# RS422_Breakout.net
KiCad netlist of a schematic drawn in Altium Designer
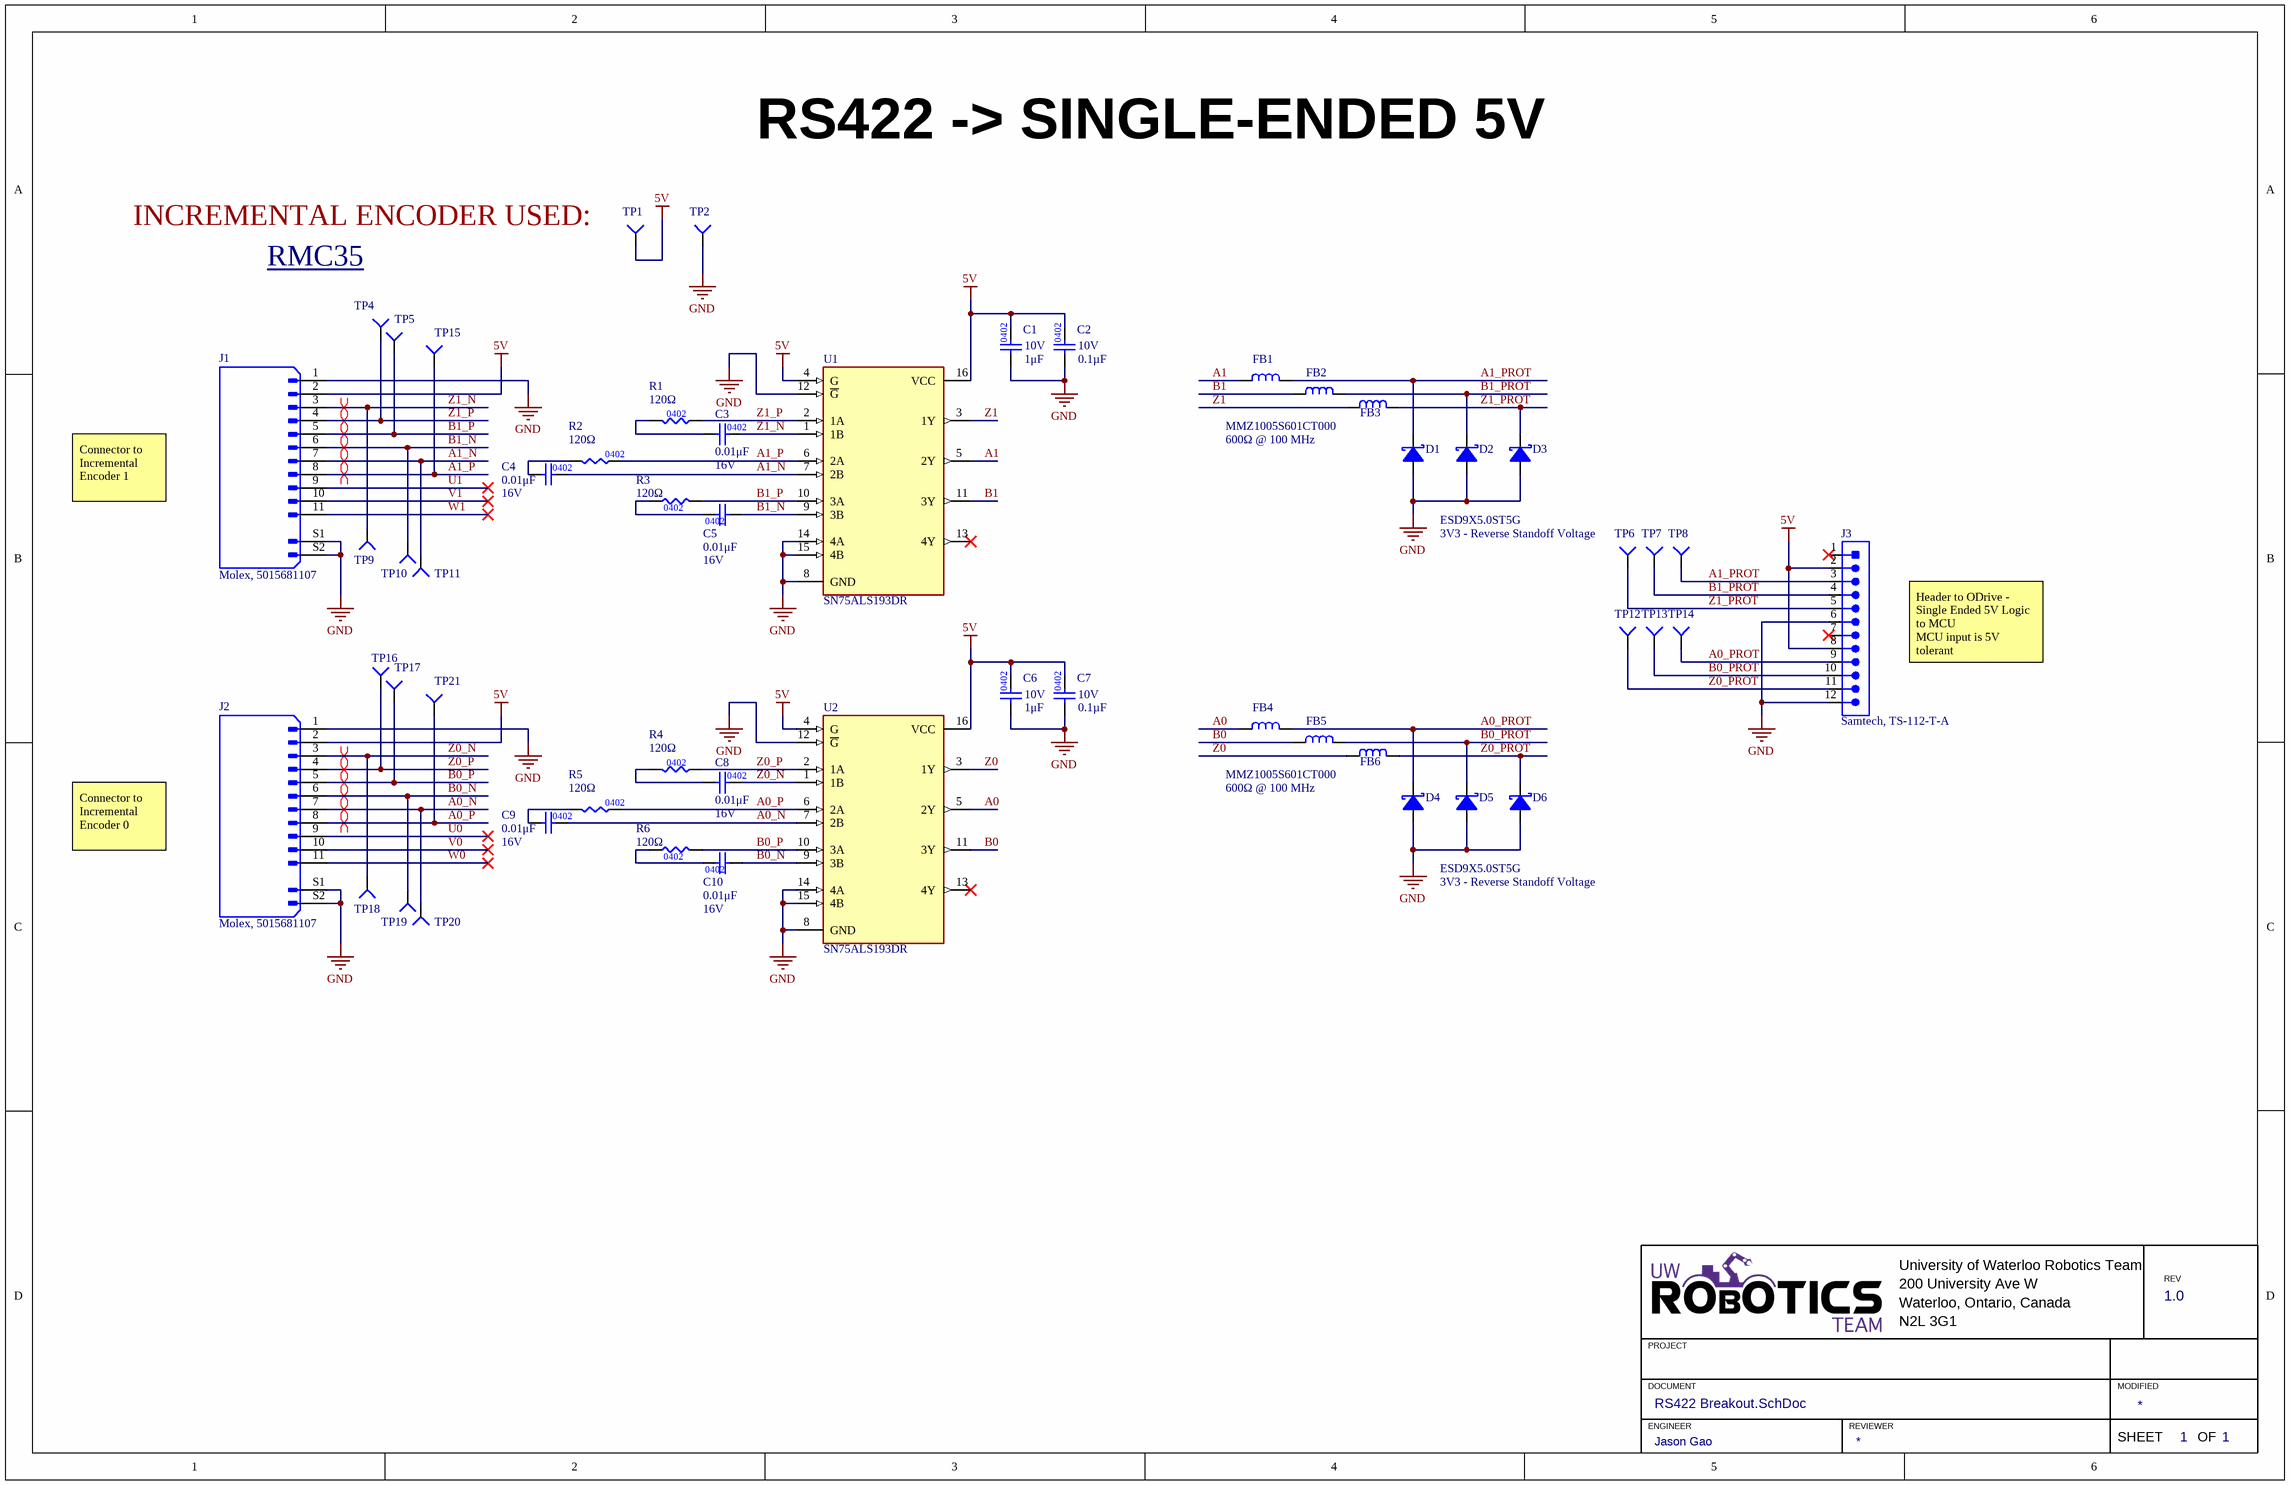
[diagram p0: RS422 Breakout.SchDoc]

(export (version "E")
  (design (tool "Eeschema 10.0.6"))
  (components
    (comp (ref "C1")
      (value "CAP_1UF_10V_0402_X5R")
      (footprint "CAP0402")
      (description "CAP CER 1UF 10V X5R 0402")
      (fields
        (field (name "MANUFACTURER") "Kyocera AVX")
        (field (name "MANUFACTURER PART NUMBER") "0402ZD105MAT2A")
        (field (name "CAPACITANCE") "1μF")
        (field (name "RATED DC VOLTAGE (URDC)") "10V")
      )
      (libsource (lib "UWRT_Schematic_Library_2020") (part "CAP_1UF_10V_0402_X5R"))
    )
    (comp (ref "C2")
      (value "0.1µF")
      (footprint "CAP0402")
      (description "CAP CER 0.1UF 10V X7R 0402")
      (fields (field (name "VOLTAGE RATING") "10V") (field (name "Comment") "CAP_0.1uF_10V_0402"))
      (libsource (lib "UWRT_Schematic_Library_2020") (part "CAP_0.1uF_10V_0402"))
    )
    (comp (ref "C3")
      (value "CAP_0.01uF_16V_X7R_0402")
      (footprint "CAP0402")
      (description "CAP CER 0.01uF 16V X7R 0402")
      (fields
        (field (name "MANUFACTURER") "KEMET")
        (field (name "MANUFACTURER PART NUMBER") "C0402C103J4RACTU")
        (field (name "CAPACITANCE") "0.01μF")
        (field (name "VOLTAGE RATING") "16V")
      )
      (libsource (lib "UWRT_Schematic_Library_2020") (part "CAP_0.01uF_16V_X7R_0402"))
    )
    (comp (ref "C4")
      (value "CAP_0.01uF_16V_X7R_0402")
      (footprint "CAP0402")
      (description "CAP CER 0.01uF 16V X7R 0402")
      (fields
        (field (name "MANUFACTURER") "KEMET")
        (field (name "MANUFACTURER PART NUMBER") "C0402C103J4RACTU")
        (field (name "CAPACITANCE") "0.01μF")
        (field (name "VOLTAGE RATING") "16V")
      )
      (libsource (lib "UWRT_Schematic_Library_2020") (part "CAP_0.01uF_16V_X7R_0402"))
    )
    (comp (ref "C5")
      (value "CAP_0.01uF_16V_X7R_0402")
      (footprint "CAP0402")
      (description "CAP CER 0.01uF 16V X7R 0402")
      (fields
        (field (name "MANUFACTURER") "KEMET")
        (field (name "MANUFACTURER PART NUMBER") "C0402C103J4RACTU")
        (field (name "CAPACITANCE") "0.01μF")
        (field (name "VOLTAGE RATING") "16V")
      )
      (libsource (lib "UWRT_Schematic_Library_2020") (part "CAP_0.01uF_16V_X7R_0402"))
    )
    (comp (ref "C6")
      (value "CAP_1UF_10V_0402_X5R")
      (footprint "CAP0402")
      (description "CAP CER 1UF 10V X5R 0402")
      (fields
        (field (name "MANUFACTURER") "Kyocera AVX")
        (field (name "MANUFACTURER PART NUMBER") "0402ZD105MAT2A")
        (field (name "CAPACITANCE") "1μF")
        (field (name "RATED DC VOLTAGE (URDC)") "10V")
      )
      (libsource (lib "UWRT_Schematic_Library_2020") (part "CAP_1UF_10V_0402_X5R"))
    )
    (comp (ref "C7")
      (value "0.1µF")
      (footprint "CAP0402")
      (description "CAP CER 0.1UF 10V X7R 0402")
      (fields (field (name "VOLTAGE RATING") "10V") (field (name "Comment") "CAP_0.1uF_10V_0402"))
      (libsource (lib "UWRT_Schematic_Library_2020") (part "CAP_0.1uF_10V_0402"))
    )
    (comp (ref "C8")
      (value "CAP_0.01uF_16V_X7R_0402")
      (footprint "CAP0402")
      (description "CAP CER 0.01uF 16V X7R 0402")
      (fields
        (field (name "MANUFACTURER") "KEMET")
        (field (name "MANUFACTURER PART NUMBER") "C0402C103J4RACTU")
        (field (name "CAPACITANCE") "0.01μF")
        (field (name "VOLTAGE RATING") "16V")
      )
      (libsource (lib "UWRT_Schematic_Library_2020") (part "CAP_0.01uF_16V_X7R_0402"))
    )
    (comp (ref "C9")
      (value "CAP_0.01uF_16V_X7R_0402")
      (footprint "CAP0402")
      (description "CAP CER 0.01uF 16V X7R 0402")
      (fields
        (field (name "MANUFACTURER") "KEMET")
        (field (name "MANUFACTURER PART NUMBER") "C0402C103J4RACTU")
        (field (name "CAPACITANCE") "0.01μF")
        (field (name "VOLTAGE RATING") "16V")
      )
      (libsource (lib "UWRT_Schematic_Library_2020") (part "CAP_0.01uF_16V_X7R_0402"))
    )
    (comp (ref "C10")
      (value "CAP_0.01uF_16V_X7R_0402")
      (footprint "CAP0402")
      (description "CAP CER 0.01uF 16V X7R 0402")
      (fields
        (field (name "MANUFACTURER") "KEMET")
        (field (name "MANUFACTURER PART NUMBER") "C0402C103J4RACTU")
        (field (name "CAPACITANCE") "0.01μF")
        (field (name "VOLTAGE RATING") "16V")
      )
      (libsource (lib "UWRT_Schematic_Library_2020") (part "CAP_0.01uF_16V_X7R_0402"))
    )
    (comp (ref "D1")
      (value "TVS_DIODE_UNIDIR_5V")
      (footprint "sod-923")
      (description "TVS DIODE 5VWM 12.3VC SOD923")
      (fields (field (name "MANUFACTURER PART NUMBER 1") "ESD9X5.0ST5G"))
      (libsource (lib "UWRT_Schematic_Library_2020") (part "TVS_DIODE_UNIDIR_5V"))
    )
    (comp (ref "D2")
      (value "TVS_DIODE_UNIDIR_5V")
      (footprint "sod-923")
      (description "TVS DIODE 5VWM 12.3VC SOD923")
      (libsource (lib "UWRT_Schematic_Library_2020") (part "TVS_DIODE_UNIDIR_5V"))
    )
    (comp (ref "D3")
      (value "TVS_DIODE_UNIDIR_5V")
      (footprint "sod-923")
      (description "TVS DIODE 5VWM 12.3VC SOD923")
      (libsource (lib "UWRT_Schematic_Library_2020") (part "TVS_DIODE_UNIDIR_5V"))
    )
    (comp (ref "D4")
      (value "TVS_DIODE_UNIDIR_5V")
      (footprint "sod-923")
      (description "TVS DIODE 5VWM 12.3VC SOD923")
      (fields (field (name "MANUFACTURER PART NUMBER 1") "ESD9X5.0ST5G"))
      (libsource (lib "UWRT_Schematic_Library_2020") (part "TVS_DIODE_UNIDIR_5V"))
    )
    (comp (ref "D5")
      (value "TVS_DIODE_UNIDIR_5V")
      (footprint "sod-923")
      (description "TVS DIODE 5VWM 12.3VC SOD923")
      (libsource (lib "UWRT_Schematic_Library_2020") (part "TVS_DIODE_UNIDIR_5V"))
    )
    (comp (ref "D6")
      (value "TVS_DIODE_UNIDIR_5V")
      (footprint "sod-923")
      (description "TVS DIODE 5VWM 12.3VC SOD923")
      (libsource (lib "UWRT_Schematic_Library_2020") (part "TVS_DIODE_UNIDIR_5V"))
    )
    (comp (ref "FB1")
      (value "FERRITE_BEAD_600OHM_0402")
      (footprint "RES0402")
      (description "FIXED IND 1UH 3.8A 33 MOHM SMD")
      (libsource (lib "UWRT_Schematic_Library_2020") (part "FERRITE_BEAD_600OHM_0402"))
    )
    (comp (ref "FB2")
      (value "FERRITE_BEAD_600OHM_0402")
      (footprint "RES0402")
      (description "FIXED IND 1UH 3.8A 33 MOHM SMD")
      (fields
        (field (name "MANUFACTURER PART NUMBER 1") "MMZ1005S601CT000")
        (field (name "IMPEDANCE @ FREQUENCY") "600Ω @ 100 MHz")
      )
      (libsource (lib "UWRT_Schematic_Library_2020") (part "FERRITE_BEAD_600OHM_0402"))
    )
    (comp (ref "FB3")
      (value "FERRITE_BEAD_600OHM_0402")
      (footprint "RES0402")
      (description "FIXED IND 1UH 3.8A 33 MOHM SMD")
      (libsource (lib "UWRT_Schematic_Library_2020") (part "FERRITE_BEAD_600OHM_0402"))
    )
    (comp (ref "FB4")
      (value "FERRITE_BEAD_600OHM_0402")
      (footprint "RES0402")
      (description "FIXED IND 1UH 3.8A 33 MOHM SMD")
      (libsource (lib "UWRT_Schematic_Library_2020") (part "FERRITE_BEAD_600OHM_0402"))
    )
    (comp (ref "FB5")
      (value "FERRITE_BEAD_600OHM_0402")
      (footprint "RES0402")
      (description "FIXED IND 1UH 3.8A 33 MOHM SMD")
      (fields
        (field (name "MANUFACTURER PART NUMBER 1") "MMZ1005S601CT000")
        (field (name "IMPEDANCE @ FREQUENCY") "600Ω @ 100 MHz")
      )
      (libsource (lib "UWRT_Schematic_Library_2020") (part "FERRITE_BEAD_600OHM_0402"))
    )
    (comp (ref "FB6")
      (value "FERRITE_BEAD_600OHM_0402")
      (footprint "RES0402")
      (description "FIXED IND 1UH 3.8A 33 MOHM SMD")
      (libsource (lib "UWRT_Schematic_Library_2020") (part "FERRITE_BEAD_600OHM_0402"))
    )
    (comp (ref "J1")
      (value "CON_12M_SM_RA")
      (footprint "MOLEX-5015681107")
      (description "CONN HEADER SMD RIGHT ANGLE 1MM PITCH")
      (fields (field (name "MP") "Molex, 5015681107"))
      (libsource (lib "templocal") (part "CON_11M_SM_RA"))
    )
    (comp (ref "J2")
      (value "CON_12M_SM_RA")
      (footprint "MOLEX-5015681107")
      (description "CONN HEADER SMD RIGHT ANGLE 1MM PITCH")
      (fields (field (name "MP") "Molex, 5015681107"))
      (libsource (lib "templocal") (part "CON_11M_SM_RA"))
    )
    (comp (ref "J3")
      (value "Samtech, TS-112-T-A")
      (footprint "Samtech-TS-112-T-A")
      (description "CONN HEADER THROUGH HOLE VERTICAL 2.54MM PITCH")
      (fields (field (name "MANUFACTURING PART NUMBER") "Samtech, TS-112-T-A"))
      (libsource (lib "UWRT_Schematic_Library_2020") (part "CON_12M_TH_VERT_2.54mm"))
    )
    (comp (ref "R1")
      (value "120Ω")
      (footprint "RES0402")
      (description "RES 120 OHM 5% 1/16W 0402")
      (fields (field (name "POWER") "1/16W") (field (name "TOLERANCE") "5%"))
      (libsource (lib "UWRT_Schematic_Library_2020") (part "RES_120Ω_0402_5%"))
    )
    (comp (ref "R2")
      (value "120Ω")
      (footprint "RES0402")
      (description "RES 120 OHM 5% 1/16W 0402")
      (fields (field (name "POWER") "1/16W") (field (name "TOLERANCE") "5%"))
      (libsource (lib "UWRT_Schematic_Library_2020") (part "RES_120Ω_0402_5%"))
    )
    (comp (ref "R3")
      (value "120Ω")
      (footprint "RES0402")
      (description "RES 120 OHM 5% 1/16W 0402")
      (fields (field (name "POWER") "1/16W") (field (name "TOLERANCE") "5%"))
      (libsource (lib "UWRT_Schematic_Library_2020") (part "RES_120Ω_0402_5%"))
    )
    (comp (ref "R4")
      (value "120Ω")
      (footprint "RES0402")
      (description "RES 120 OHM 5% 1/16W 0402")
      (fields (field (name "POWER") "1/16W") (field (name "TOLERANCE") "5%"))
      (libsource (lib "UWRT_Schematic_Library_2020") (part "RES_120Ω_0402_5%"))
    )
    (comp (ref "R5")
      (value "120Ω")
      (footprint "RES0402")
      (description "RES 120 OHM 5% 1/16W 0402")
      (fields (field (name "POWER") "1/16W") (field (name "TOLERANCE") "5%"))
      (libsource (lib "UWRT_Schematic_Library_2020") (part "RES_120Ω_0402_5%"))
    )
    (comp (ref "R6")
      (value "120Ω")
      (footprint "RES0402")
      (description "RES 120 OHM 5% 1/16W 0402")
      (fields (field (name "POWER") "1/16W") (field (name "TOLERANCE") "5%"))
      (libsource (lib "UWRT_Schematic_Library_2020") (part "RES_120Ω_0402_5%"))
    )
    (comp (ref "TP1")
      (value "TESTPOINT_SMD_LOOP")
      (footprint "S1751-46R")
      (description "TESTPOINT SMD LOOP")
      (libsource (lib "UWRT_Schematic_Library_2020") (part "TESTPOINT_SMD_LOOP"))
    )
    (comp (ref "TP2")
      (value "TESTPOINT_SMD_LOOP")
      (footprint "S1751-46R")
      (description "TESTPOINT SMD LOOP")
      (libsource (lib "UWRT_Schematic_Library_2020") (part "TESTPOINT_SMD_LOOP"))
    )
    (comp (ref "TP4")
      (value "TESTPOINT_1MM_SQUARE")
      (footprint "TESTPOINT_SQUARE_1MM")
      (description "TESTPOINT 1MM SQUARE")
      (libsource (lib "UWRT_Schematic_Library_2020") (part "TESTPOINT_1MM_SQUARE"))
    )
    (comp (ref "TP5")
      (value "TESTPOINT_1MM_SQUARE")
      (footprint "TESTPOINT_SQUARE_1MM")
      (description "TESTPOINT 1MM SQUARE")
      (libsource (lib "UWRT_Schematic_Library_2020") (part "TESTPOINT_1MM_SQUARE"))
    )
    (comp (ref "TP6")
      (value "TESTPOINT_1MM_CIRCLE")
      (footprint "TESTPOINT_CIRCLE_1MM")
      (description "TESTPOINT 1MM CIRCLE")
      (libsource (lib "UWRT_Schematic_Library_2020") (part "TESTPOINT_1MM_CIRCLE"))
    )
    (comp (ref "TP7")
      (value "TESTPOINT_1MM_CIRCLE")
      (footprint "TESTPOINT_CIRCLE_1MM")
      (description "TESTPOINT 1MM CIRCLE")
      (libsource (lib "UWRT_Schematic_Library_2020") (part "TESTPOINT_1MM_CIRCLE"))
    )
    (comp (ref "TP8")
      (value "TESTPOINT_1MM_CIRCLE")
      (footprint "TESTPOINT_CIRCLE_1MM")
      (description "TESTPOINT 1MM CIRCLE")
      (libsource (lib "UWRT_Schematic_Library_2020") (part "TESTPOINT_1MM_CIRCLE"))
    )
    (comp (ref "TP9")
      (value "TESTPOINT_1MM_CIRCLE")
      (footprint "TESTPOINT_CIRCLE_1MM")
      (description "TESTPOINT 1MM CIRCLE")
      (libsource (lib "UWRT_Schematic_Library_2020") (part "TESTPOINT_1MM_CIRCLE"))
    )
    (comp (ref "TP10")
      (value "TESTPOINT_1MM_CIRCLE")
      (footprint "TESTPOINT_CIRCLE_1MM")
      (description "TESTPOINT 1MM CIRCLE")
      (libsource (lib "UWRT_Schematic_Library_2020") (part "TESTPOINT_1MM_CIRCLE"))
    )
    (comp (ref "TP11")
      (value "TESTPOINT_1MM_CIRCLE")
      (footprint "TESTPOINT_CIRCLE_1MM")
      (description "TESTPOINT 1MM CIRCLE")
      (libsource (lib "UWRT_Schematic_Library_2020") (part "TESTPOINT_1MM_CIRCLE"))
    )
    (comp (ref "TP12")
      (value "TESTPOINT_1MM_CIRCLE")
      (footprint "TESTPOINT_CIRCLE_1MM")
      (description "TESTPOINT 1MM CIRCLE")
      (libsource (lib "UWRT_Schematic_Library_2020") (part "TESTPOINT_1MM_CIRCLE"))
    )
    (comp (ref "TP13")
      (value "TESTPOINT_1MM_CIRCLE")
      (footprint "TESTPOINT_CIRCLE_1MM")
      (description "TESTPOINT 1MM CIRCLE")
      (libsource (lib "UWRT_Schematic_Library_2020") (part "TESTPOINT_1MM_CIRCLE"))
    )
    (comp (ref "TP14")
      (value "TESTPOINT_1MM_CIRCLE")
      (footprint "TESTPOINT_CIRCLE_1MM")
      (description "TESTPOINT 1MM CIRCLE")
      (libsource (lib "UWRT_Schematic_Library_2020") (part "TESTPOINT_1MM_CIRCLE"))
    )
    (comp (ref "TP15")
      (value "TESTPOINT_1MM_SQUARE")
      (footprint "TESTPOINT_SQUARE_1MM")
      (description "TESTPOINT 1MM SQUARE")
      (libsource (lib "UWRT_Schematic_Library_2020") (part "TESTPOINT_1MM_SQUARE"))
    )
    (comp (ref "TP16")
      (value "TESTPOINT_1MM_SQUARE")
      (footprint "TESTPOINT_SQUARE_1MM")
      (description "TESTPOINT 1MM SQUARE")
      (libsource (lib "UWRT_Schematic_Library_2020") (part "TESTPOINT_1MM_SQUARE"))
    )
    (comp (ref "TP17")
      (value "TESTPOINT_1MM_SQUARE")
      (footprint "TESTPOINT_SQUARE_1MM")
      (description "TESTPOINT 1MM SQUARE")
      (libsource (lib "UWRT_Schematic_Library_2020") (part "TESTPOINT_1MM_SQUARE"))
    )
    (comp (ref "TP18")
      (value "TESTPOINT_1MM_CIRCLE")
      (footprint "TESTPOINT_CIRCLE_1MM")
      (description "TESTPOINT 1MM CIRCLE")
      (libsource (lib "UWRT_Schematic_Library_2020") (part "TESTPOINT_1MM_CIRCLE"))
    )
    (comp (ref "TP19")
      (value "TESTPOINT_1MM_CIRCLE")
      (footprint "TESTPOINT_CIRCLE_1MM")
      (description "TESTPOINT 1MM CIRCLE")
      (libsource (lib "UWRT_Schematic_Library_2020") (part "TESTPOINT_1MM_CIRCLE"))
    )
    (comp (ref "TP20")
      (value "TESTPOINT_1MM_CIRCLE")
      (footprint "TESTPOINT_CIRCLE_1MM")
      (description "TESTPOINT 1MM CIRCLE")
      (libsource (lib "UWRT_Schematic_Library_2020") (part "TESTPOINT_1MM_CIRCLE"))
    )
    (comp (ref "TP21")
      (value "TESTPOINT_1MM_SQUARE")
      (footprint "TESTPOINT_SQUARE_1MM")
      (description "TESTPOINT 1MM SQUARE")
      (libsource (lib "UWRT_Schematic_Library_2020") (part "TESTPOINT_1MM_SQUARE"))
    )
    (comp (ref "U1")
      (value "SN75ALS193DR")
      (footprint "SOIC127P600X175-16N")
      (description "0/4 Receiver - RS422, RS423 16-SOIC")
      (fields (field (name "COPYRIGHT") "Copyright (C) 2021 Ultra Librarian. All rights reserved."))
      (libsource (lib "UWRT_Schematic_Library_2020") (part "SN75ALS193DR"))
    )
    (comp (ref "U2")
      (value "SN75ALS193DR")
      (footprint "SOIC127P600X175-16N")
      (description "0/4 Receiver - RS422, RS423 16-SOIC")
      (fields (field (name "COPYRIGHT") "Copyright (C) 2021 Ultra Librarian. All rights reserved."))
      (libsource (lib "UWRT_Schematic_Library_2020") (part "SN75ALS193DR"))
    )
  )
  (nets
    (net (code "1") (name "/A0") (class "Default")
      (node (ref "FB4") (pin "1") (pinfunction "1_1") (pintype "passive"))
      (node (ref "U2") (pin "5") (pinfunction "2Y_5") (pintype "output"))
    )
    (net (code "2") (name "/A0_N") (class "Default")
      (node (ref "C9") (pin "2") (pinfunction "2_2") (pintype "passive"))
      (node (ref "J2") (pin "7") (pinfunction "7_7") (pintype "passive"))
      (node (ref "TP20") (pin "1") (pinfunction "=value_1") (pintype "passive"))
      (node (ref "U2") (pin "7") (pinfunction "2B_7") (pintype "input"))
    )
    (net (code "3") (name "/A0_P") (class "Default")
      (node (ref "J2") (pin "8") (pinfunction "8_8") (pintype "passive"))
      (node (ref "R5") (pin "2") (pinfunction "2_2") (pintype "passive"))
      (node (ref "TP21") (pin "1") (pinfunction "=value_1") (pintype "passive"))
      (node (ref "U2") (pin "6") (pinfunction "2A_6") (pintype "input"))
    )
    (net (code "4") (name "/A0_PROT") (class "Default")
      (node (ref "D4") (pin "1") (pinfunction "Cathode_1") (pintype "passive"))
      (node (ref "FB4") (pin "2") (pinfunction "2_2") (pintype "passive"))
      (node (ref "J3") (pin "9") (pinfunction "3_9") (pintype "passive"))
      (node (ref "TP14") (pin "1") (pinfunction "=value_1") (pintype "passive"))
    )
    (net (code "5") (name "/A1") (class "Default")
      (node (ref "FB1") (pin "1") (pinfunction "1_1") (pintype "passive"))
      (node (ref "U1") (pin "5") (pinfunction "2Y_5") (pintype "output"))
    )
    (net (code "6") (name "/A1_N") (class "Default")
      (node (ref "C4") (pin "2") (pinfunction "2_2") (pintype "passive"))
      (node (ref "J1") (pin "7") (pinfunction "7_7") (pintype "passive"))
      (node (ref "TP11") (pin "1") (pinfunction "=value_1") (pintype "passive"))
      (node (ref "U1") (pin "7") (pinfunction "2B_7") (pintype "input"))
    )
    (net (code "7") (name "/A1_P") (class "Default")
      (node (ref "J1") (pin "8") (pinfunction "8_8") (pintype "passive"))
      (node (ref "R2") (pin "2") (pinfunction "2_2") (pintype "passive"))
      (node (ref "TP15") (pin "1") (pinfunction "=value_1") (pintype "passive"))
      (node (ref "U1") (pin "6") (pinfunction "2A_6") (pintype "input"))
    )
    (net (code "8") (name "/A1_PROT") (class "Default")
      (node (ref "D1") (pin "1") (pinfunction "Cathode_1") (pintype "passive"))
      (node (ref "FB1") (pin "2") (pinfunction "2_2") (pintype "passive"))
      (node (ref "J3") (pin "3") (pinfunction "3_3") (pintype "passive"))
      (node (ref "TP8") (pin "1") (pinfunction "=value_1") (pintype "passive"))
    )
    (net (code "9") (name "/B0") (class "Default")
      (node (ref "FB5") (pin "1") (pinfunction "1_1") (pintype "passive"))
      (node (ref "U2") (pin "11") (pinfunction "3Y_11") (pintype "output"))
    )
    (net (code "10") (name "/B0_N") (class "Default")
      (node (ref "C10") (pin "2") (pinfunction "2_2") (pintype "passive"))
      (node (ref "J2") (pin "6") (pinfunction "6_6") (pintype "passive"))
      (node (ref "TP19") (pin "1") (pinfunction "=value_1") (pintype "passive"))
      (node (ref "U2") (pin "9") (pinfunction "3B_9") (pintype "input"))
    )
    (net (code "11") (name "/B0_P") (class "Default")
      (node (ref "J2") (pin "5") (pinfunction "5_5") (pintype "passive"))
      (node (ref "R6") (pin "2") (pinfunction "2_2") (pintype "passive"))
      (node (ref "TP17") (pin "1") (pinfunction "=value_1") (pintype "passive"))
      (node (ref "U2") (pin "10") (pinfunction "3A_10") (pintype "input"))
    )
    (net (code "12") (name "/B0_PROT") (class "Default")
      (node (ref "D5") (pin "1") (pinfunction "Cathode_1") (pintype "passive"))
      (node (ref "FB5") (pin "2") (pinfunction "2_2") (pintype "passive"))
      (node (ref "J3") (pin "10") (pinfunction "4_10") (pintype "passive"))
      (node (ref "TP13") (pin "1") (pinfunction "=value_1") (pintype "passive"))
    )
    (net (code "13") (name "/B1") (class "Default")
      (node (ref "FB2") (pin "1") (pinfunction "1_1") (pintype "passive"))
      (node (ref "U1") (pin "11") (pinfunction "3Y_11") (pintype "output"))
    )
    (net (code "14") (name "/B1_N") (class "Default")
      (node (ref "C5") (pin "2") (pinfunction "2_2") (pintype "passive"))
      (node (ref "J1") (pin "6") (pinfunction "6_6") (pintype "passive"))
      (node (ref "TP10") (pin "1") (pinfunction "=value_1") (pintype "passive"))
      (node (ref "U1") (pin "9") (pinfunction "3B_9") (pintype "input"))
    )
    (net (code "15") (name "/B1_P") (class "Default")
      (node (ref "J1") (pin "5") (pinfunction "5_5") (pintype "passive"))
      (node (ref "R3") (pin "2") (pinfunction "2_2") (pintype "passive"))
      (node (ref "TP5") (pin "1") (pinfunction "=value_1") (pintype "passive"))
      (node (ref "U1") (pin "10") (pinfunction "3A_10") (pintype "input"))
    )
    (net (code "16") (name "/B1_PROT") (class "Default")
      (node (ref "D2") (pin "1") (pinfunction "Cathode_1") (pintype "passive"))
      (node (ref "FB2") (pin "2") (pinfunction "2_2") (pintype "passive"))
      (node (ref "J3") (pin "4") (pinfunction "4_4") (pintype "passive"))
      (node (ref "TP7") (pin "1") (pinfunction "=value_1") (pintype "passive"))
    )
    (net (code "17") (name "/U0") (class "Default")
      (node (ref "J2") (pin "9") (pinfunction "9_9") (pintype "passive+no_connect"))
    )
    (net (code "18") (name "/U1") (class "Default")
      (node (ref "J1") (pin "9") (pinfunction "9_9") (pintype "passive+no_connect"))
    )
    (net (code "19") (name "/V0") (class "Default")
      (node (ref "J2") (pin "10") (pinfunction "10_10") (pintype "passive+no_connect"))
    )
    (net (code "20") (name "/V1") (class "Default")
      (node (ref "J1") (pin "10") (pinfunction "10_10") (pintype "passive+no_connect"))
    )
    (net (code "21") (name "/W0") (class "Default")
      (node (ref "J2") (pin "11") (pinfunction "11_11") (pintype "passive+no_connect"))
    )
    (net (code "22") (name "/W1") (class "Default")
      (node (ref "J1") (pin "11") (pinfunction "11_11") (pintype "passive+no_connect"))
    )
    (net (code "23") (name "/Z0") (class "Default")
      (node (ref "FB6") (pin "1") (pinfunction "1_1") (pintype "passive"))
      (node (ref "U2") (pin "3") (pinfunction "1Y_3") (pintype "output"))
    )
    (net (code "24") (name "/Z0_N") (class "Default")
      (node (ref "C8") (pin "2") (pinfunction "2_2") (pintype "passive"))
      (node (ref "J2") (pin "3") (pinfunction "3_3") (pintype "passive"))
      (node (ref "TP18") (pin "1") (pinfunction "=value_1") (pintype "passive"))
      (node (ref "U2") (pin "1") (pinfunction "1B_1") (pintype "input"))
    )
    (net (code "25") (name "/Z0_P") (class "Default")
      (node (ref "J2") (pin "4") (pinfunction "4_4") (pintype "passive"))
      (node (ref "R4") (pin "1") (pinfunction "1_1") (pintype "passive"))
      (node (ref "TP16") (pin "1") (pinfunction "=value_1") (pintype "passive"))
      (node (ref "U2") (pin "2") (pinfunction "1A_2") (pintype "input"))
    )
    (net (code "26") (name "/Z0_PROT") (class "Default")
      (node (ref "D6") (pin "1") (pinfunction "Cathode_1") (pintype "passive"))
      (node (ref "FB6") (pin "2") (pinfunction "2_2") (pintype "passive"))
      (node (ref "J3") (pin "11") (pinfunction "5_11") (pintype "passive"))
      (node (ref "TP12") (pin "1") (pinfunction "=value_1") (pintype "passive"))
    )
    (net (code "27") (name "/Z1") (class "Default")
      (node (ref "FB3") (pin "1") (pinfunction "1_1") (pintype "passive"))
      (node (ref "U1") (pin "3") (pinfunction "1Y_3") (pintype "output"))
    )
    (net (code "28") (name "/Z1_N") (class "Default")
      (node (ref "C3") (pin "2") (pinfunction "2_2") (pintype "passive"))
      (node (ref "J1") (pin "3") (pinfunction "3_3") (pintype "passive"))
      (node (ref "TP9") (pin "1") (pinfunction "=value_1") (pintype "passive"))
      (node (ref "U1") (pin "1") (pinfunction "1B_1") (pintype "input"))
    )
    (net (code "29") (name "/Z1_P") (class "Default")
      (node (ref "J1") (pin "4") (pinfunction "4_4") (pintype "passive"))
      (node (ref "R1") (pin "1") (pinfunction "1_1") (pintype "passive"))
      (node (ref "TP4") (pin "1") (pinfunction "=value_1") (pintype "passive"))
      (node (ref "U1") (pin "2") (pinfunction "1A_2") (pintype "input"))
    )
    (net (code "30") (name "/Z1_PROT") (class "Default")
      (node (ref "D3") (pin "1") (pinfunction "Cathode_1") (pintype "passive"))
      (node (ref "FB3") (pin "2") (pinfunction "2_2") (pintype "passive"))
      (node (ref "J3") (pin "5") (pinfunction "5_5") (pintype "passive"))
      (node (ref "TP6") (pin "1") (pinfunction "=value_1") (pintype "passive"))
    )
    (net (code "31") (name "5V") (class "Default")
      (node (ref "C1") (pin "2") (pinfunction "2_2") (pintype "passive"))
      (node (ref "C2") (pin "2") (pinfunction "2_2") (pintype "passive"))
      (node (ref "C6") (pin "2") (pinfunction "2_2") (pintype "passive"))
      (node (ref "C7") (pin "2") (pinfunction "2_2") (pintype "passive"))
      (node (ref "J1") (pin "2") (pinfunction "2_2") (pintype "passive"))
      (node (ref "J2") (pin "2") (pinfunction "2_2") (pintype "passive"))
      (node (ref "J3") (pin "2") (pinfunction "2_2") (pintype "passive"))
      (node (ref "J3") (pin "8") (pinfunction "2_8") (pintype "passive"))
      (node (ref "TP1") (pin "1") (pinfunction "=value_1") (pintype "passive"))
      (node (ref "U1") (pin "16") (pinfunction "VCC_16") (pintype "power_in"))
      (node (ref "U1") (pin "4") (pinfunction "G_4") (pintype "input"))
      (node (ref "U2") (pin "16") (pinfunction "VCC_16") (pintype "power_in"))
      (node (ref "U2") (pin "4") (pinfunction "G_4") (pintype "input"))
    )
    (net (code "32") (name "GND") (class "Default")
      (node (ref "C1") (pin "1") (pinfunction "1_1") (pintype "passive"))
      (node (ref "C2") (pin "1") (pinfunction "1_1") (pintype "passive"))
      (node (ref "C6") (pin "1") (pinfunction "1_1") (pintype "passive"))
      (node (ref "C7") (pin "1") (pinfunction "1_1") (pintype "passive"))
      (node (ref "D1") (pin "2") (pinfunction "Anode_2") (pintype "passive"))
      (node (ref "D2") (pin "2") (pinfunction "Anode_2") (pintype "passive"))
      (node (ref "D3") (pin "2") (pinfunction "Anode_2") (pintype "passive"))
      (node (ref "D4") (pin "2") (pinfunction "Anode_2") (pintype "passive"))
      (node (ref "D5") (pin "2") (pinfunction "Anode_2") (pintype "passive"))
      (node (ref "D6") (pin "2") (pinfunction "Anode_2") (pintype "passive"))
      (node (ref "J1") (pin "1") (pinfunction "1_1") (pintype "passive"))
      (node (ref "J1") (pin "S1") (pinfunction "SHIELD1_S1") (pintype "passive"))
      (node (ref "J1") (pin "S2") (pinfunction "SHIELD2_S2") (pintype "passive"))
      (node (ref "J2") (pin "1") (pinfunction "1_1") (pintype "passive"))
      (node (ref "J2") (pin "S1") (pinfunction "SHIELD1_S1") (pintype "passive"))
      (node (ref "J2") (pin "S2") (pinfunction "SHIELD2_S2") (pintype "passive"))
      (node (ref "J3") (pin "12") (pinfunction "6_12") (pintype "passive"))
      (node (ref "J3") (pin "6") (pinfunction "6_6") (pintype "passive"))
      (node (ref "TP2") (pin "1") (pinfunction "=value_1") (pintype "passive"))
      (node (ref "U1") (pin "12") (pinfunction "~{G}_12") (pintype "input"))
      (node (ref "U1") (pin "14") (pinfunction "4A_14") (pintype "input"))
      (node (ref "U1") (pin "15") (pinfunction "4B_15") (pintype "input"))
      (node (ref "U1") (pin "8") (pinfunction "GND_8") (pintype "power_in"))
      (node (ref "U2") (pin "12") (pinfunction "~{G}_12") (pintype "input"))
      (node (ref "U2") (pin "14") (pinfunction "4A_14") (pintype "input"))
      (node (ref "U2") (pin "15") (pinfunction "4B_15") (pintype "input"))
      (node (ref "U2") (pin "8") (pinfunction "GND_8") (pintype "power_in"))
    )
    (net (code "33") (name "Net-(C3-Pad1)") (class "Default")
      (node (ref "C3") (pin "1") (pinfunction "1_1") (pintype "passive"))
      (node (ref "R1") (pin "2") (pinfunction "2_2") (pintype "passive"))
    )
    (net (code "34") (name "Net-(C4-Pad1)") (class "Default")
      (node (ref "C4") (pin "1") (pinfunction "1_1") (pintype "passive"))
      (node (ref "R2") (pin "1") (pinfunction "1_1") (pintype "passive"))
    )
    (net (code "35") (name "Net-(C5-Pad1)") (class "Default")
      (node (ref "C5") (pin "1") (pinfunction "1_1") (pintype "passive"))
      (node (ref "R3") (pin "1") (pinfunction "1_1") (pintype "passive"))
    )
    (net (code "36") (name "Net-(C8-Pad1)") (class "Default")
      (node (ref "C8") (pin "1") (pinfunction "1_1") (pintype "passive"))
      (node (ref "R4") (pin "2") (pinfunction "2_2") (pintype "passive"))
    )
    (net (code "37") (name "Net-(C9-Pad1)") (class "Default")
      (node (ref "C9") (pin "1") (pinfunction "1_1") (pintype "passive"))
      (node (ref "R5") (pin "1") (pinfunction "1_1") (pintype "passive"))
    )
    (net (code "38") (name "Net-(C10-Pad1)") (class "Default")
      (node (ref "C10") (pin "1") (pinfunction "1_1") (pintype "passive"))
      (node (ref "R6") (pin "1") (pinfunction "1_1") (pintype "passive"))
    )
    (net (code "39") (name "unconnected-(J3-1-Pad7)") (class "Default")
      (node (ref "J3") (pin "7") (pinfunction "1_7") (pintype "passive+no_connect"))
    )
    (net (code "40") (name "unconnected-(J3-Pad1)") (class "Default")
      (node (ref "J3") (pin "1") (pinfunction "1_1") (pintype "passive+no_connect"))
    )
    (net (code "41") (name "unconnected-(U1-4Y-Pad13)") (class "Default")
      (node (ref "U1") (pin "13") (pinfunction "4Y_13") (pintype "output+no_connect"))
    )
    (net (code "42") (name "unconnected-(U2-4Y-Pad13)") (class "Default")
      (node (ref "U2") (pin "13") (pinfunction "4Y_13") (pintype "output+no_connect"))
    )
  )
)
